# vela.net
KiCad netlist of a schematic drawn in EAGLE
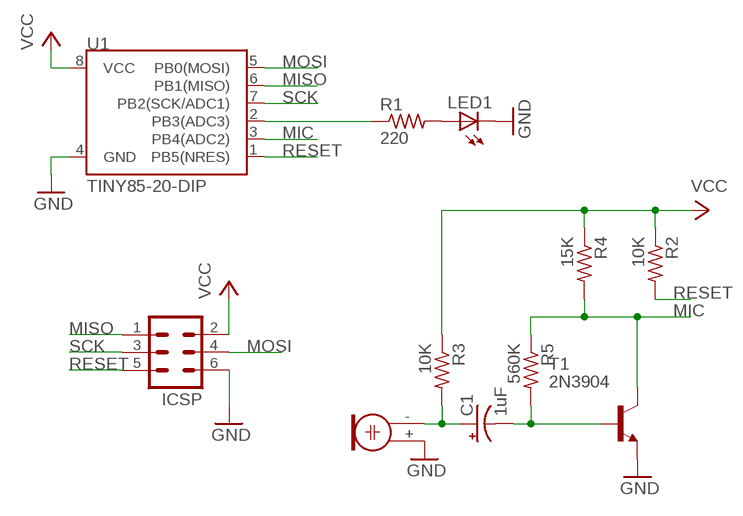
[diagram p0: schematic, sheet 1]

(export (version "E")
  (design (tool "Eeschema 10.0.6"))
  (components
    (comp (ref "C1")
      (value "1uF")
      (footprint "eagle-import:E2-5")
      (libsource (lib "eagle-import") (part "CPOL-USE2-5"))
    )
    (comp (ref "ICSP")
      (value "MA03-2")
      (footprint "eagle-import:MA03-2")
      (libsource (lib "eagle-import") (part "MA03-2"))
    )
    (comp (ref "LED1")
      (value "LED5MM")
      (footprint "eagle-import:LED5MM")
      (libsource (lib "eagle-import") (part "LED5MM"))
    )
    (comp (ref "M1")
      (value "ELECTRET_MICROPHON-TOM-1545P-R")
      (footprint "eagle-import:TOM-1545P-R")
      (libsource (lib "eagle-import") (part "ELECTRET_MICROPHON-TOM-1545P-R"))
    )
    (comp (ref "R1")
      (value "220")
      (footprint "eagle-import:0207_2V")
      (libsource (lib "eagle-import") (part "R-US_0207/2V"))
    )
    (comp (ref "R2")
      (value "10K")
      (footprint "eagle-import:0207_2V")
      (libsource (lib "eagle-import") (part "R-US_0207/2V"))
    )
    (comp (ref "R3")
      (value "10K")
      (footprint "eagle-import:0207_2V")
      (libsource (lib "eagle-import") (part "R-US_0207/2V"))
    )
    (comp (ref "R4")
      (value "15K")
      (footprint "eagle-import:0207_2V")
      (libsource (lib "eagle-import") (part "R-US_0207/2V"))
    )
    (comp (ref "R5")
      (value "560K")
      (footprint "eagle-import:0207_2V")
      (libsource (lib "eagle-import") (part "R-US_0207/2V"))
    )
    (comp (ref "T1")
      (value "2N3904")
      (footprint "eagle-import:TO92")
      (libsource (lib "eagle-import") (part "2N3904"))
    )
    (comp (ref "U1")
      (value "TINY85-20-DIP")
      (footprint "eagle-import:DIP08")
      (libsource (lib "eagle-import") (part "ATTINY45TINY85-20-DIP"))
    )
  )
  (nets
    (net (code "1") (name "/MIC") (class "Default")
      (node (ref "R4") (pin "2") (pinfunction "2_2") (pintype "passive"))
      (node (ref "R5") (pin "1") (pinfunction "1_1") (pintype "passive"))
      (node (ref "T1") (pin "1") (pinfunction "C_1") (pintype "passive"))
      (node (ref "U1") (pin "3") (pinfunction "PB4(ADC2)_3") (pintype "bidirectional"))
    )
    (net (code "2") (name "/MISO") (class "Default")
      (node (ref "ICSP") (pin "1") (pinfunction "1_1") (pintype "passive"))
      (node (ref "U1") (pin "6") (pinfunction "PB1(MISO)_6") (pintype "bidirectional"))
    )
    (net (code "3") (name "/MOSI") (class "Default")
      (node (ref "ICSP") (pin "4") (pinfunction "4_4") (pintype "passive"))
      (node (ref "U1") (pin "5") (pinfunction "PB0(MOSI)_5") (pintype "bidirectional"))
    )
    (net (code "4") (name "/RESET") (class "Default")
      (node (ref "ICSP") (pin "5") (pinfunction "5_5") (pintype "passive"))
      (node (ref "R2") (pin "2") (pinfunction "2_2") (pintype "passive"))
      (node (ref "U1") (pin "1") (pinfunction "PB5(NRES)_1") (pintype "bidirectional"))
    )
    (net (code "5") (name "/SCK") (class "Default")
      (node (ref "ICSP") (pin "3") (pinfunction "3_3") (pintype "passive"))
      (node (ref "U1") (pin "7") (pinfunction "PB2(SCK/ADC1)_7") (pintype "bidirectional"))
    )
    (net (code "6") (name "GND") (class "Default")
      (node (ref "ICSP") (pin "6") (pinfunction "6_6") (pintype "passive"))
      (node (ref "LED1") (pin "K") (pinfunction "C_K") (pintype "passive"))
      (node (ref "M1") (pin "+") (pinfunction "1_+") (pintype "passive"))
      (node (ref "T1") (pin "3") (pinfunction "E_3") (pintype "passive"))
      (node (ref "U1") (pin "4") (pinfunction "GND_4") (pintype "bidirectional"))
    )
    (net (code "7") (name "Net-(LED1-PadA)") (class "Default")
      (node (ref "LED1") (pin "A") (pinfunction "A_A") (pintype "passive"))
      (node (ref "R1") (pin "2") (pinfunction "2_2") (pintype "passive"))
    )
    (net (code "8") (name "Net-(M1-2)") (class "Default")
      (node (ref "C1") (pin "+") (pinfunction "+_+") (pintype "passive"))
      (node (ref "M1") (pin "-") (pinfunction "2_-") (pintype "passive"))
      (node (ref "R3") (pin "2") (pinfunction "2_2") (pintype "passive"))
    )
    (net (code "9") (name "Net-(T1-B)") (class "Default")
      (node (ref "C1") (pin "-") (pinfunction "-_-") (pintype "passive"))
      (node (ref "R5") (pin "2") (pinfunction "2_2") (pintype "passive"))
      (node (ref "T1") (pin "2") (pinfunction "B_2") (pintype "passive"))
    )
    (net (code "10") (name "Net-(U1-PB3(ADC3))") (class "Default")
      (node (ref "R1") (pin "1") (pinfunction "1_1") (pintype "passive"))
      (node (ref "U1") (pin "2") (pinfunction "PB3(ADC3)_2") (pintype "bidirectional"))
    )
    (net (code "11") (name "VCC") (class "Default")
      (node (ref "ICSP") (pin "2") (pinfunction "2_2") (pintype "passive"))
      (node (ref "R2") (pin "1") (pinfunction "1_1") (pintype "passive"))
      (node (ref "R3") (pin "1") (pinfunction "1_1") (pintype "passive"))
      (node (ref "R4") (pin "1") (pinfunction "1_1") (pintype "passive"))
      (node (ref "U1") (pin "8") (pinfunction "VCC_8") (pintype "bidirectional"))
    )
  )
)
